# light_sensor.net
KiCad netlist of a schematic drawn in EAGLE
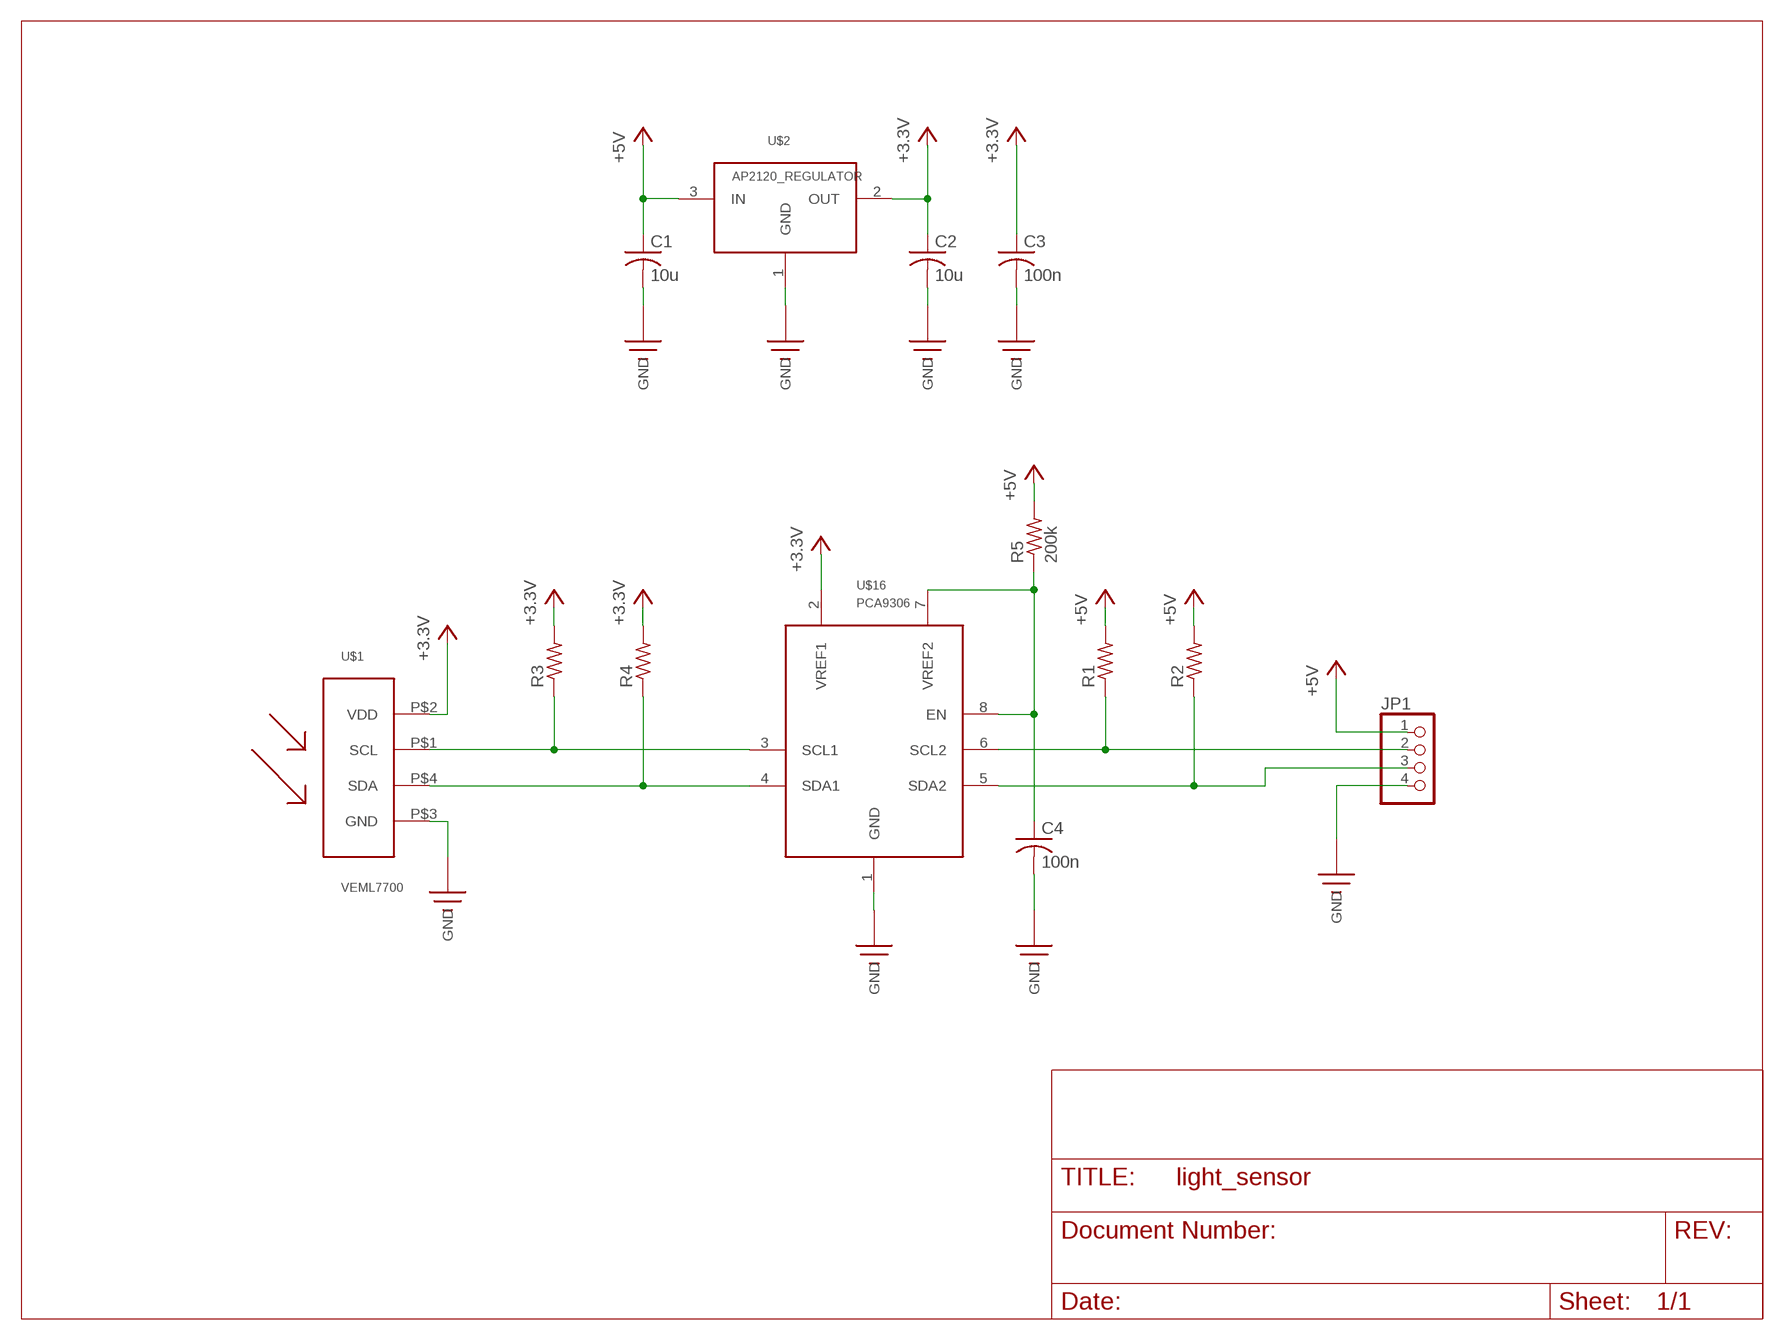
[diagram p0: schematic, sheet 1]

(export (version "E")
  (design (tool "Eeschema 10.0.6"))
  (components
    (comp (ref "C1")
      (value "10u")
      (footprint "eagle-import:C1206K")
      (libsource (lib "eagle-import") (part "C-USC1206K"))
    )
    (comp (ref "C2")
      (value "10u")
      (footprint "eagle-import:C1206K")
      (libsource (lib "eagle-import") (part "C-USC1206K"))
    )
    (comp (ref "C3")
      (value "100n")
      (footprint "eagle-import:C0603K")
      (libsource (lib "eagle-import") (part "C-USC0603K"))
    )
    (comp (ref "C4")
      (value "100n")
      (footprint "eagle-import:C0603K")
      (libsource (lib "eagle-import") (part "C-USC0603K"))
    )
    (comp (ref "JP1")
      (value "PINHD-1X4")
      (footprint "eagle-import:1X04")
      (libsource (lib "eagle-import") (part "PINHD-1X4"))
    )
    (comp (ref "R1")
      (value "R-US_R0603")
      (footprint "eagle-import:R0603")
      (libsource (lib "eagle-import") (part "R-US_R0603"))
    )
    (comp (ref "R2")
      (value "R-US_R0603")
      (footprint "eagle-import:R0603")
      (libsource (lib "eagle-import") (part "R-US_R0603"))
    )
    (comp (ref "R3")
      (value "R-US_R0603")
      (footprint "eagle-import:R0603")
      (libsource (lib "eagle-import") (part "R-US_R0603"))
    )
    (comp (ref "R4")
      (value "R-US_R0603")
      (footprint "eagle-import:R0603")
      (libsource (lib "eagle-import") (part "R-US_R0603"))
    )
    (comp (ref "R5")
      (value "200k")
      (footprint "eagle-import:R0603")
      (libsource (lib "eagle-import") (part "R-US_R0603"))
    )
    (comp (ref "U$1")
      (value "VEML7700")
      (footprint "eagle-import:VEML7700_SIDE")
      (libsource (lib "eagle-import") (part "VEML7700"))
    )
    (comp (ref "U$2")
      (value "AP2120_REGULATOR")
      (footprint "eagle-import:SOT23")
      (libsource (lib "eagle-import") (part "AP2120_REGULATOR"))
    )
    (comp (ref "U$16")
      (value "PCA9306")
      (footprint "eagle-import:SO08")
      (libsource (lib "eagle-import") (part "PCA9306"))
    )
  )
  (nets
    (net (code "1") (name "+3.3V") (class "Default")
      (node (ref "C2") (pin "1") (pinfunction "1_1") (pintype "passive"))
      (node (ref "C3") (pin "1") (pinfunction "1_1") (pintype "passive"))
      (node (ref "R3") (pin "2") (pinfunction "2_2") (pintype "passive"))
      (node (ref "R4") (pin "2") (pinfunction "2_2") (pintype "passive"))
      (node (ref "U$1") (pin "P$2") (pinfunction "VDD_P$2") (pintype "bidirectional"))
      (node (ref "U$16") (pin "2") (pinfunction "VREF1_2") (pintype "bidirectional"))
      (node (ref "U$2") (pin "2") (pinfunction "OUT_2") (pintype "bidirectional"))
    )
    (net (code "2") (name "+5V") (class "Default")
      (node (ref "C1") (pin "1") (pinfunction "1_1") (pintype "passive"))
      (node (ref "JP1") (pin "1") (pinfunction "1_1") (pintype "passive"))
      (node (ref "R1") (pin "2") (pinfunction "2_2") (pintype "passive"))
      (node (ref "R2") (pin "2") (pinfunction "2_2") (pintype "passive"))
      (node (ref "R5") (pin "2") (pinfunction "2_2") (pintype "passive"))
      (node (ref "U$2") (pin "3") (pinfunction "IN_3") (pintype "bidirectional"))
    )
    (net (code "3") (name "GND") (class "Default")
      (node (ref "C1") (pin "2") (pinfunction "2_2") (pintype "passive"))
      (node (ref "C2") (pin "2") (pinfunction "2_2") (pintype "passive"))
      (node (ref "C3") (pin "2") (pinfunction "2_2") (pintype "passive"))
      (node (ref "C4") (pin "2") (pinfunction "2_2") (pintype "passive"))
      (node (ref "JP1") (pin "4") (pinfunction "4_4") (pintype "passive"))
      (node (ref "U$1") (pin "P$3") (pinfunction "GND_P$3") (pintype "bidirectional"))
      (node (ref "U$16") (pin "1") (pinfunction "GND_1") (pintype "bidirectional"))
      (node (ref "U$2") (pin "1") (pinfunction "GND_1") (pintype "bidirectional"))
    )
    (net (code "4") (name "Net-(U$1-SCL)") (class "Default")
      (node (ref "R3") (pin "1") (pinfunction "1_1") (pintype "passive"))
      (node (ref "U$1") (pin "P$1") (pinfunction "SCL_P$1") (pintype "bidirectional"))
      (node (ref "U$16") (pin "3") (pinfunction "SCL1_3") (pintype "bidirectional"))
    )
    (net (code "5") (name "Net-(U$1-SDA)") (class "Default")
      (node (ref "R4") (pin "1") (pinfunction "1_1") (pintype "passive"))
      (node (ref "U$1") (pin "P$4") (pinfunction "SDA_P$4") (pintype "bidirectional"))
      (node (ref "U$16") (pin "4") (pinfunction "SDA1_4") (pintype "bidirectional"))
    )
    (net (code "6") (name "Net-(U$16-EN)") (class "Default")
      (node (ref "C4") (pin "1") (pinfunction "1_1") (pintype "passive"))
      (node (ref "R5") (pin "1") (pinfunction "1_1") (pintype "passive"))
      (node (ref "U$16") (pin "7") (pinfunction "VREF2_7") (pintype "bidirectional"))
      (node (ref "U$16") (pin "8") (pinfunction "EN_8") (pintype "bidirectional"))
    )
    (net (code "7") (name "Net-(U$16-SCL2)") (class "Default")
      (node (ref "JP1") (pin "2") (pinfunction "2_2") (pintype "passive"))
      (node (ref "R1") (pin "1") (pinfunction "1_1") (pintype "passive"))
      (node (ref "U$16") (pin "6") (pinfunction "SCL2_6") (pintype "bidirectional"))
    )
    (net (code "8") (name "Net-(U$16-SDA2)") (class "Default")
      (node (ref "JP1") (pin "3") (pinfunction "3_3") (pintype "passive"))
      (node (ref "R2") (pin "1") (pinfunction "1_1") (pintype "passive"))
      (node (ref "U$16") (pin "5") (pinfunction "SDA2_5") (pintype "bidirectional"))
    )
  )
)
